# Connectors.net
KiCad netlist of a schematic drawn in Altium Designer
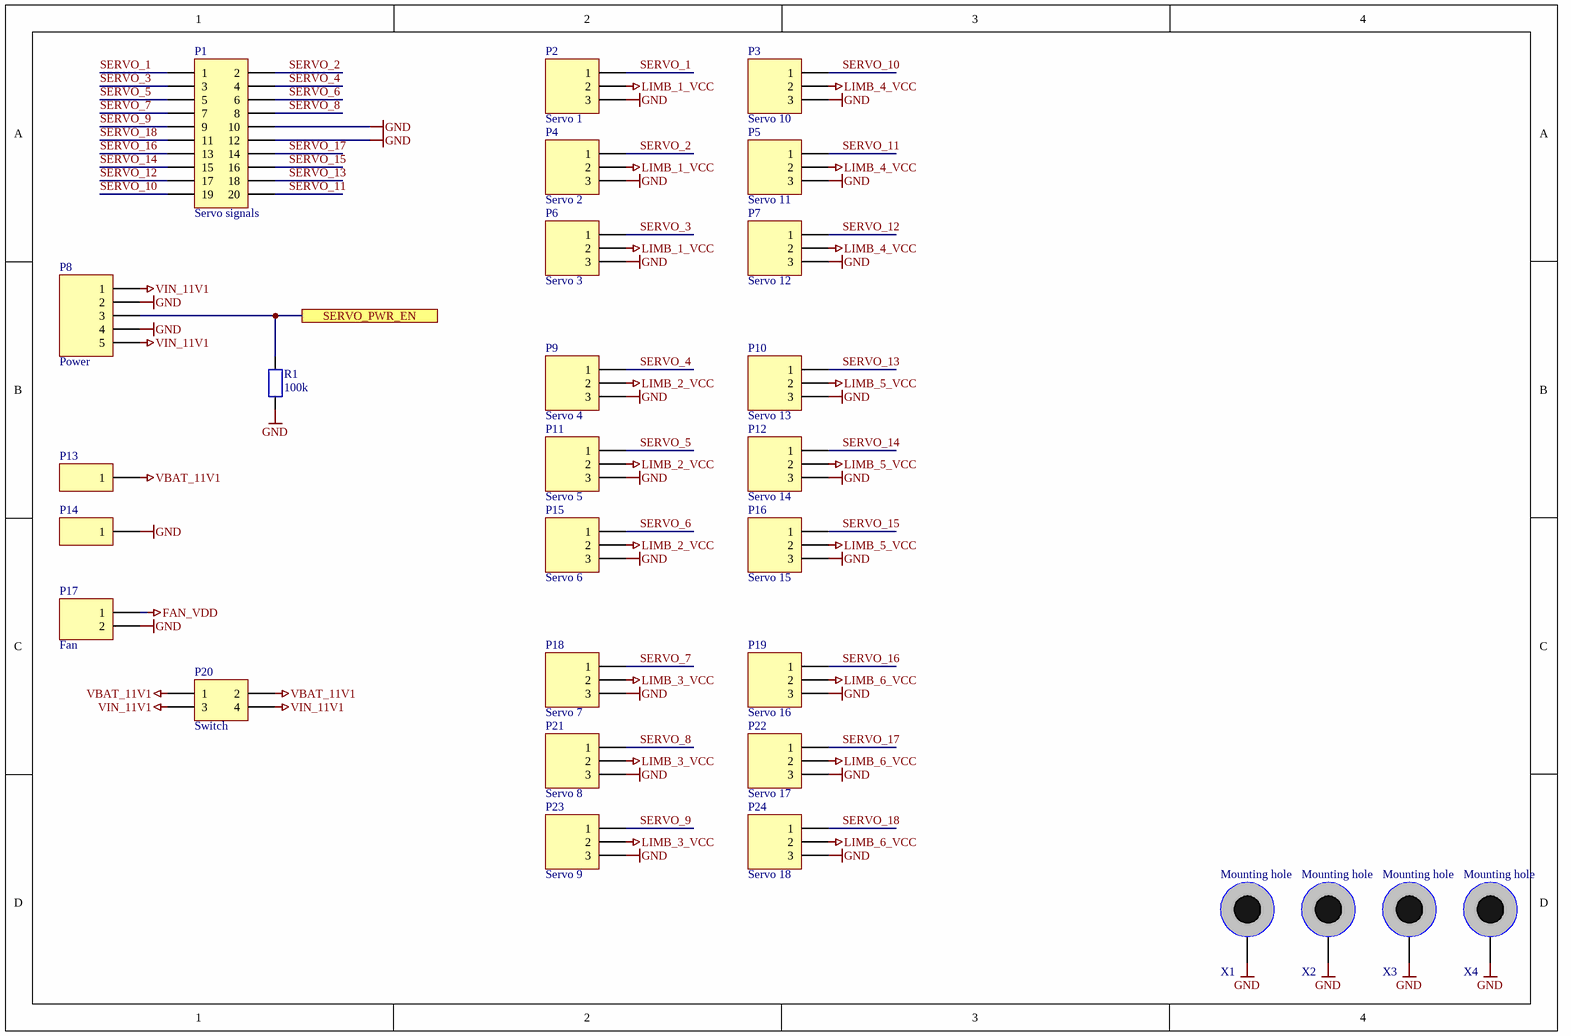
[diagram p0: Connectors.SchDoc]

(export (version "E")
  (design (tool "Eeschema 10.0.6"))
  (components
    (comp (ref "P1")
      (value "Servo signals")
      (footprint "IDC-20")
      (description "Header, 2x10-Pin")
      (fields (field (name "PUBLISHER") "Altium Limited"))
      (libsource (lib "connectors") (part "Header 2x10"))
    )
    (comp (ref "P2")
      (value "Servo 1")
      (footprint "PLS-3 2.54")
      (description "Header, 3-Pin")
      (fields (field (name "PUBLISHER") "Altium Limited"))
      (libsource (lib "connectors") (part "Header 3"))
    )
    (comp (ref "P3")
      (value "Servo 10")
      (footprint "PLS-3 2.54")
      (description "Header, 3-Pin")
      (fields (field (name "PUBLISHER") "Altium Limited"))
      (libsource (lib "connectors") (part "Header 3"))
    )
    (comp (ref "P4")
      (value "Servo 2")
      (footprint "PLS-3 2.54")
      (description "Header, 3-Pin")
      (fields (field (name "PUBLISHER") "Altium Limited"))
      (libsource (lib "connectors") (part "Header 3"))
    )
    (comp (ref "P5")
      (value "Servo 11")
      (footprint "PLS-3 2.54")
      (description "Header, 3-Pin")
      (fields (field (name "PUBLISHER") "Altium Limited"))
      (libsource (lib "connectors") (part "Header 3"))
    )
    (comp (ref "P6")
      (value "Servo 3")
      (footprint "PLS-3 2.54")
      (description "Header, 3-Pin")
      (fields (field (name "PUBLISHER") "Altium Limited"))
      (libsource (lib "connectors") (part "Header 3"))
    )
    (comp (ref "P7")
      (value "Servo 12")
      (footprint "PLS-3 2.54")
      (description "Header, 3-Pin")
      (fields (field (name "PUBLISHER") "Altium Limited"))
      (libsource (lib "connectors") (part "Header 3"))
    )
    (comp (ref "P8")
      (value "Power")
      (footprint "PLS-5 2.54")
      (description "Header, 5-Pin")
      (fields (field (name "PUBLISHER") "Altium Limited"))
      (libsource (lib "connectors") (part "Header 5"))
    )
    (comp (ref "P9")
      (value "Servo 4")
      (footprint "PLS-3 2.54")
      (description "Header, 3-Pin")
      (fields (field (name "PUBLISHER") "Altium Limited"))
      (libsource (lib "connectors") (part "Header 3"))
    )
    (comp (ref "P10")
      (value "Servo 13")
      (footprint "PLS-3 2.54")
      (description "Header, 3-Pin")
      (fields (field (name "PUBLISHER") "Altium Limited"))
      (libsource (lib "connectors") (part "Header 3"))
    )
    (comp (ref "P11")
      (value "Servo 5")
      (footprint "PLS-3 2.54")
      (description "Header, 3-Pin")
      (fields (field (name "PUBLISHER") "Altium Limited"))
      (libsource (lib "connectors") (part "Header 3"))
    )
    (comp (ref "P12")
      (value "Servo 14")
      (footprint "PLS-3 2.54")
      (description "Header, 3-Pin")
      (fields (field (name "PUBLISHER") "Altium Limited"))
      (libsource (lib "connectors") (part "Header 3"))
    )
    (comp (ref "P13")
      (value "~")
      (footprint "WIRE_SMD_5X5")
      (description "Header, 1-Pin")
      (fields (field (name "PUBLISHER") "Altium Limited"))
      (libsource (lib "connectors") (part "Header 1"))
    )
    (comp (ref "P14")
      (value "~")
      (footprint "WIRE_SMD_5X5")
      (description "Header, 1-Pin")
      (fields (field (name "PUBLISHER") "Altium Limited"))
      (libsource (lib "connectors") (part "Header 1"))
    )
    (comp (ref "P15")
      (value "Servo 6")
      (footprint "PLS-3 2.54")
      (description "Header, 3-Pin")
      (fields (field (name "PUBLISHER") "Altium Limited"))
      (libsource (lib "connectors") (part "Header 3"))
    )
    (comp (ref "P16")
      (value "Servo 15")
      (footprint "PLS-3 2.54")
      (description "Header, 3-Pin")
      (fields (field (name "PUBLISHER") "Altium Limited"))
      (libsource (lib "connectors") (part "Header 3"))
    )
    (comp (ref "P17")
      (value "Fan")
      (footprint "PLS-2 2.54")
      (description "Header, 2-Pin")
      (fields (field (name "PUBLISHER") "Altium Limited"))
      (libsource (lib "connectors") (part "Header 2"))
    )
    (comp (ref "P18")
      (value "Servo 7")
      (footprint "PLS-3 2.54")
      (description "Header, 3-Pin")
      (fields (field (name "PUBLISHER") "Altium Limited"))
      (libsource (lib "connectors") (part "Header 3"))
    )
    (comp (ref "P19")
      (value "Servo 16")
      (footprint "PLS-3 2.54")
      (description "Header, 3-Pin")
      (fields (field (name "PUBLISHER") "Altium Limited"))
      (libsource (lib "connectors") (part "Header 3"))
    )
    (comp (ref "P20")
      (value "Switch")
      (footprint "PLD-2 2.54")
      (description "Header, 2-Pin")
      (fields (field (name "PUBLISHER") "Altium Limited"))
      (libsource (lib "connectors") (part "Header 2x2"))
    )
    (comp (ref "P21")
      (value "Servo 8")
      (footprint "PLS-3 2.54")
      (description "Header, 3-Pin")
      (fields (field (name "PUBLISHER") "Altium Limited"))
      (libsource (lib "connectors") (part "Header 3"))
    )
    (comp (ref "P22")
      (value "Servo 17")
      (footprint "PLS-3 2.54")
      (description "Header, 3-Pin")
      (fields (field (name "PUBLISHER") "Altium Limited"))
      (libsource (lib "connectors") (part "Header 3"))
    )
    (comp (ref "P23")
      (value "Servo 9")
      (footprint "PLS-3 2.54")
      (description "Header, 3-Pin")
      (fields (field (name "PUBLISHER") "Altium Limited"))
      (libsource (lib "connectors") (part "Header 3"))
    )
    (comp (ref "P24")
      (value "Servo 18")
      (footprint "PLS-3 2.54")
      (description "Header, 3-Pin")
      (fields (field (name "PUBLISHER") "Altium Limited"))
      (libsource (lib "connectors") (part "Header 3"))
    )
    (comp (ref "R1")
      (value "100k")
      (footprint "R_0603/1608")
      (description "Resistor")
      (libsource (lib "passive") (part "Resistor"))
    )
    (comp (ref "X1")
      (value "Mounting hole")
      (footprint "HOLE_M3_D6.0/3.5")
      (description "Hole for screw M3, outline D6")
      (libsource (lib "connectors") (part "Mounting hole"))
    )
    (comp (ref "X2")
      (value "Mounting hole")
      (footprint "HOLE_M3_D6.0/3.5")
      (description "Hole for screw M3, outline D6")
      (libsource (lib "connectors") (part "Mounting hole"))
    )
    (comp (ref "X3")
      (value "Mounting hole")
      (footprint "HOLE_M3_D6.0/3.5")
      (description "Hole for screw M3, outline D6")
      (libsource (lib "connectors") (part "Mounting hole"))
    )
    (comp (ref "X4")
      (value "Mounting hole")
      (footprint "HOLE_M3_D6.0/3.5")
      (description "Hole for screw M3, outline D6")
      (libsource (lib "connectors") (part "Mounting hole"))
    )
  )
  (nets
    (net (code "1") (name "/SERVO_1") (class "Default")
      (node (ref "P1") (pin "1") (pinfunction "1_1") (pintype "passive"))
      (node (ref "P2") (pin "1") (pinfunction "1_1") (pintype "passive"))
    )
    (net (code "2") (name "/SERVO_2") (class "Default")
      (node (ref "P1") (pin "2") (pinfunction "2_2") (pintype "passive"))
      (node (ref "P4") (pin "1") (pinfunction "1_1") (pintype "passive"))
    )
    (net (code "3") (name "/SERVO_3") (class "Default")
      (node (ref "P1") (pin "3") (pinfunction "3_3") (pintype "passive"))
      (node (ref "P6") (pin "1") (pinfunction "1_1") (pintype "passive"))
    )
    (net (code "4") (name "/SERVO_4") (class "Default")
      (node (ref "P1") (pin "4") (pinfunction "4_4") (pintype "passive"))
      (node (ref "P9") (pin "1") (pinfunction "1_1") (pintype "passive"))
    )
    (net (code "5") (name "/SERVO_5") (class "Default")
      (node (ref "P1") (pin "5") (pinfunction "5_5") (pintype "passive"))
      (node (ref "P11") (pin "1") (pinfunction "1_1") (pintype "passive"))
    )
    (net (code "6") (name "/SERVO_6") (class "Default")
      (node (ref "P1") (pin "6") (pinfunction "6_6") (pintype "passive"))
      (node (ref "P15") (pin "1") (pinfunction "1_1") (pintype "passive"))
    )
    (net (code "7") (name "/SERVO_7") (class "Default")
      (node (ref "P1") (pin "7") (pinfunction "7_7") (pintype "passive"))
      (node (ref "P18") (pin "1") (pinfunction "1_1") (pintype "passive"))
    )
    (net (code "8") (name "/SERVO_8") (class "Default")
      (node (ref "P1") (pin "8") (pinfunction "8_8") (pintype "passive"))
      (node (ref "P21") (pin "1") (pinfunction "1_1") (pintype "passive"))
    )
    (net (code "9") (name "/SERVO_9") (class "Default")
      (node (ref "P1") (pin "9") (pinfunction "9_9") (pintype "passive"))
      (node (ref "P23") (pin "1") (pinfunction "1_1") (pintype "passive"))
    )
    (net (code "10") (name "/SERVO_10") (class "Default")
      (node (ref "P1") (pin "19") (pinfunction "19_19") (pintype "passive"))
      (node (ref "P3") (pin "1") (pinfunction "1_1") (pintype "passive"))
    )
    (net (code "11") (name "/SERVO_11") (class "Default")
      (node (ref "P1") (pin "20") (pinfunction "20_20") (pintype "passive"))
      (node (ref "P5") (pin "1") (pinfunction "1_1") (pintype "passive"))
    )
    (net (code "12") (name "/SERVO_12") (class "Default")
      (node (ref "P1") (pin "17") (pinfunction "17_17") (pintype "passive"))
      (node (ref "P7") (pin "1") (pinfunction "1_1") (pintype "passive"))
    )
    (net (code "13") (name "/SERVO_13") (class "Default")
      (node (ref "P1") (pin "18") (pinfunction "18_18") (pintype "passive"))
      (node (ref "P10") (pin "1") (pinfunction "1_1") (pintype "passive"))
    )
    (net (code "14") (name "/SERVO_14") (class "Default")
      (node (ref "P1") (pin "15") (pinfunction "15_15") (pintype "passive"))
      (node (ref "P12") (pin "1") (pinfunction "1_1") (pintype "passive"))
    )
    (net (code "15") (name "/SERVO_15") (class "Default")
      (node (ref "P1") (pin "16") (pinfunction "16_16") (pintype "passive"))
      (node (ref "P16") (pin "1") (pinfunction "1_1") (pintype "passive"))
    )
    (net (code "16") (name "/SERVO_16") (class "Default")
      (node (ref "P1") (pin "13") (pinfunction "13_13") (pintype "passive"))
      (node (ref "P19") (pin "1") (pinfunction "1_1") (pintype "passive"))
    )
    (net (code "17") (name "/SERVO_17") (class "Default")
      (node (ref "P1") (pin "14") (pinfunction "14_14") (pintype "passive"))
      (node (ref "P22") (pin "1") (pinfunction "1_1") (pintype "passive"))
    )
    (net (code "18") (name "/SERVO_18") (class "Default")
      (node (ref "P1") (pin "11") (pinfunction "11_11") (pintype "passive"))
      (node (ref "P24") (pin "1") (pinfunction "1_1") (pintype "passive"))
    )
    (net (code "19") (name "/SERVO_PWR_EN") (class "Default")
      (node (ref "P8") (pin "3") (pinfunction "3_3") (pintype "passive"))
      (node (ref "R1") (pin "1") (pintype "passive"))
    )
    (net (code "20") (name "FAN_VDD") (class "Default")
      (node (ref "P17") (pin "1") (pinfunction "1_1") (pintype "passive"))
    )
    (net (code "21") (name "GND") (class "Default")
      (node (ref "P1") (pin "10") (pinfunction "10_10") (pintype "passive"))
      (node (ref "P1") (pin "12") (pinfunction "12_12") (pintype "passive"))
      (node (ref "P10") (pin "3") (pinfunction "3_3") (pintype "passive"))
      (node (ref "P11") (pin "3") (pinfunction "3_3") (pintype "passive"))
      (node (ref "P12") (pin "3") (pinfunction "3_3") (pintype "passive"))
      (node (ref "P14") (pin "1") (pinfunction "1_1") (pintype "passive"))
      (node (ref "P15") (pin "3") (pinfunction "3_3") (pintype "passive"))
      (node (ref "P16") (pin "3") (pinfunction "3_3") (pintype "passive"))
      (node (ref "P17") (pin "2") (pinfunction "2_2") (pintype "passive"))
      (node (ref "P18") (pin "3") (pinfunction "3_3") (pintype "passive"))
      (node (ref "P19") (pin "3") (pinfunction "3_3") (pintype "passive"))
      (node (ref "P2") (pin "3") (pinfunction "3_3") (pintype "passive"))
      (node (ref "P21") (pin "3") (pinfunction "3_3") (pintype "passive"))
      (node (ref "P22") (pin "3") (pinfunction "3_3") (pintype "passive"))
      (node (ref "P23") (pin "3") (pinfunction "3_3") (pintype "passive"))
      (node (ref "P24") (pin "3") (pinfunction "3_3") (pintype "passive"))
      (node (ref "P3") (pin "3") (pinfunction "3_3") (pintype "passive"))
      (node (ref "P4") (pin "3") (pinfunction "3_3") (pintype "passive"))
      (node (ref "P5") (pin "3") (pinfunction "3_3") (pintype "passive"))
      (node (ref "P6") (pin "3") (pinfunction "3_3") (pintype "passive"))
      (node (ref "P7") (pin "3") (pinfunction "3_3") (pintype "passive"))
      (node (ref "P8") (pin "2") (pinfunction "2_2") (pintype "passive"))
      (node (ref "P8") (pin "4") (pinfunction "4_4") (pintype "passive"))
      (node (ref "P9") (pin "3") (pinfunction "3_3") (pintype "passive"))
      (node (ref "R1") (pin "2") (pintype "passive"))
      (node (ref "X1") (pin "1") (pintype "passive"))
      (node (ref "X2") (pin "1") (pintype "passive"))
      (node (ref "X3") (pin "1") (pintype "passive"))
      (node (ref "X4") (pin "1") (pintype "passive"))
    )
    (net (code "22") (name "LIMB_1_VCC") (class "Default")
      (node (ref "P2") (pin "2") (pinfunction "2_2") (pintype "passive"))
      (node (ref "P4") (pin "2") (pinfunction "2_2") (pintype "passive"))
      (node (ref "P6") (pin "2") (pinfunction "2_2") (pintype "passive"))
    )
    (net (code "23") (name "LIMB_2_VCC") (class "Default")
      (node (ref "P11") (pin "2") (pinfunction "2_2") (pintype "passive"))
      (node (ref "P15") (pin "2") (pinfunction "2_2") (pintype "passive"))
      (node (ref "P9") (pin "2") (pinfunction "2_2") (pintype "passive"))
    )
    (net (code "24") (name "LIMB_3_VCC") (class "Default")
      (node (ref "P18") (pin "2") (pinfunction "2_2") (pintype "passive"))
      (node (ref "P21") (pin "2") (pinfunction "2_2") (pintype "passive"))
      (node (ref "P23") (pin "2") (pinfunction "2_2") (pintype "passive"))
    )
    (net (code "25") (name "LIMB_4_VCC") (class "Default")
      (node (ref "P3") (pin "2") (pinfunction "2_2") (pintype "passive"))
      (node (ref "P5") (pin "2") (pinfunction "2_2") (pintype "passive"))
      (node (ref "P7") (pin "2") (pinfunction "2_2") (pintype "passive"))
    )
    (net (code "26") (name "LIMB_5_VCC") (class "Default")
      (node (ref "P10") (pin "2") (pinfunction "2_2") (pintype "passive"))
      (node (ref "P12") (pin "2") (pinfunction "2_2") (pintype "passive"))
      (node (ref "P16") (pin "2") (pinfunction "2_2") (pintype "passive"))
    )
    (net (code "27") (name "LIMB_6_VCC") (class "Default")
      (node (ref "P19") (pin "2") (pinfunction "2_2") (pintype "passive"))
      (node (ref "P22") (pin "2") (pinfunction "2_2") (pintype "passive"))
      (node (ref "P24") (pin "2") (pinfunction "2_2") (pintype "passive"))
    )
    (net (code "28") (name "VBAT_11V1") (class "Default")
      (node (ref "P13") (pin "1") (pinfunction "1_1") (pintype "passive"))
      (node (ref "P20") (pin "1") (pinfunction "1_1") (pintype "passive"))
      (node (ref "P20") (pin "2") (pinfunction "2_2") (pintype "passive"))
    )
    (net (code "29") (name "VIN_11V1") (class "Default")
      (node (ref "P20") (pin "3") (pinfunction "3_3") (pintype "passive"))
      (node (ref "P20") (pin "4") (pinfunction "4_4") (pintype "passive"))
      (node (ref "P8") (pin "1") (pinfunction "1_1") (pintype "passive"))
      (node (ref "P8") (pin "5") (pinfunction "5_5") (pintype "passive"))
    )
  )
)
